# P04-NET.net
KiCad netlist of a schematic drawn in Altium Designer
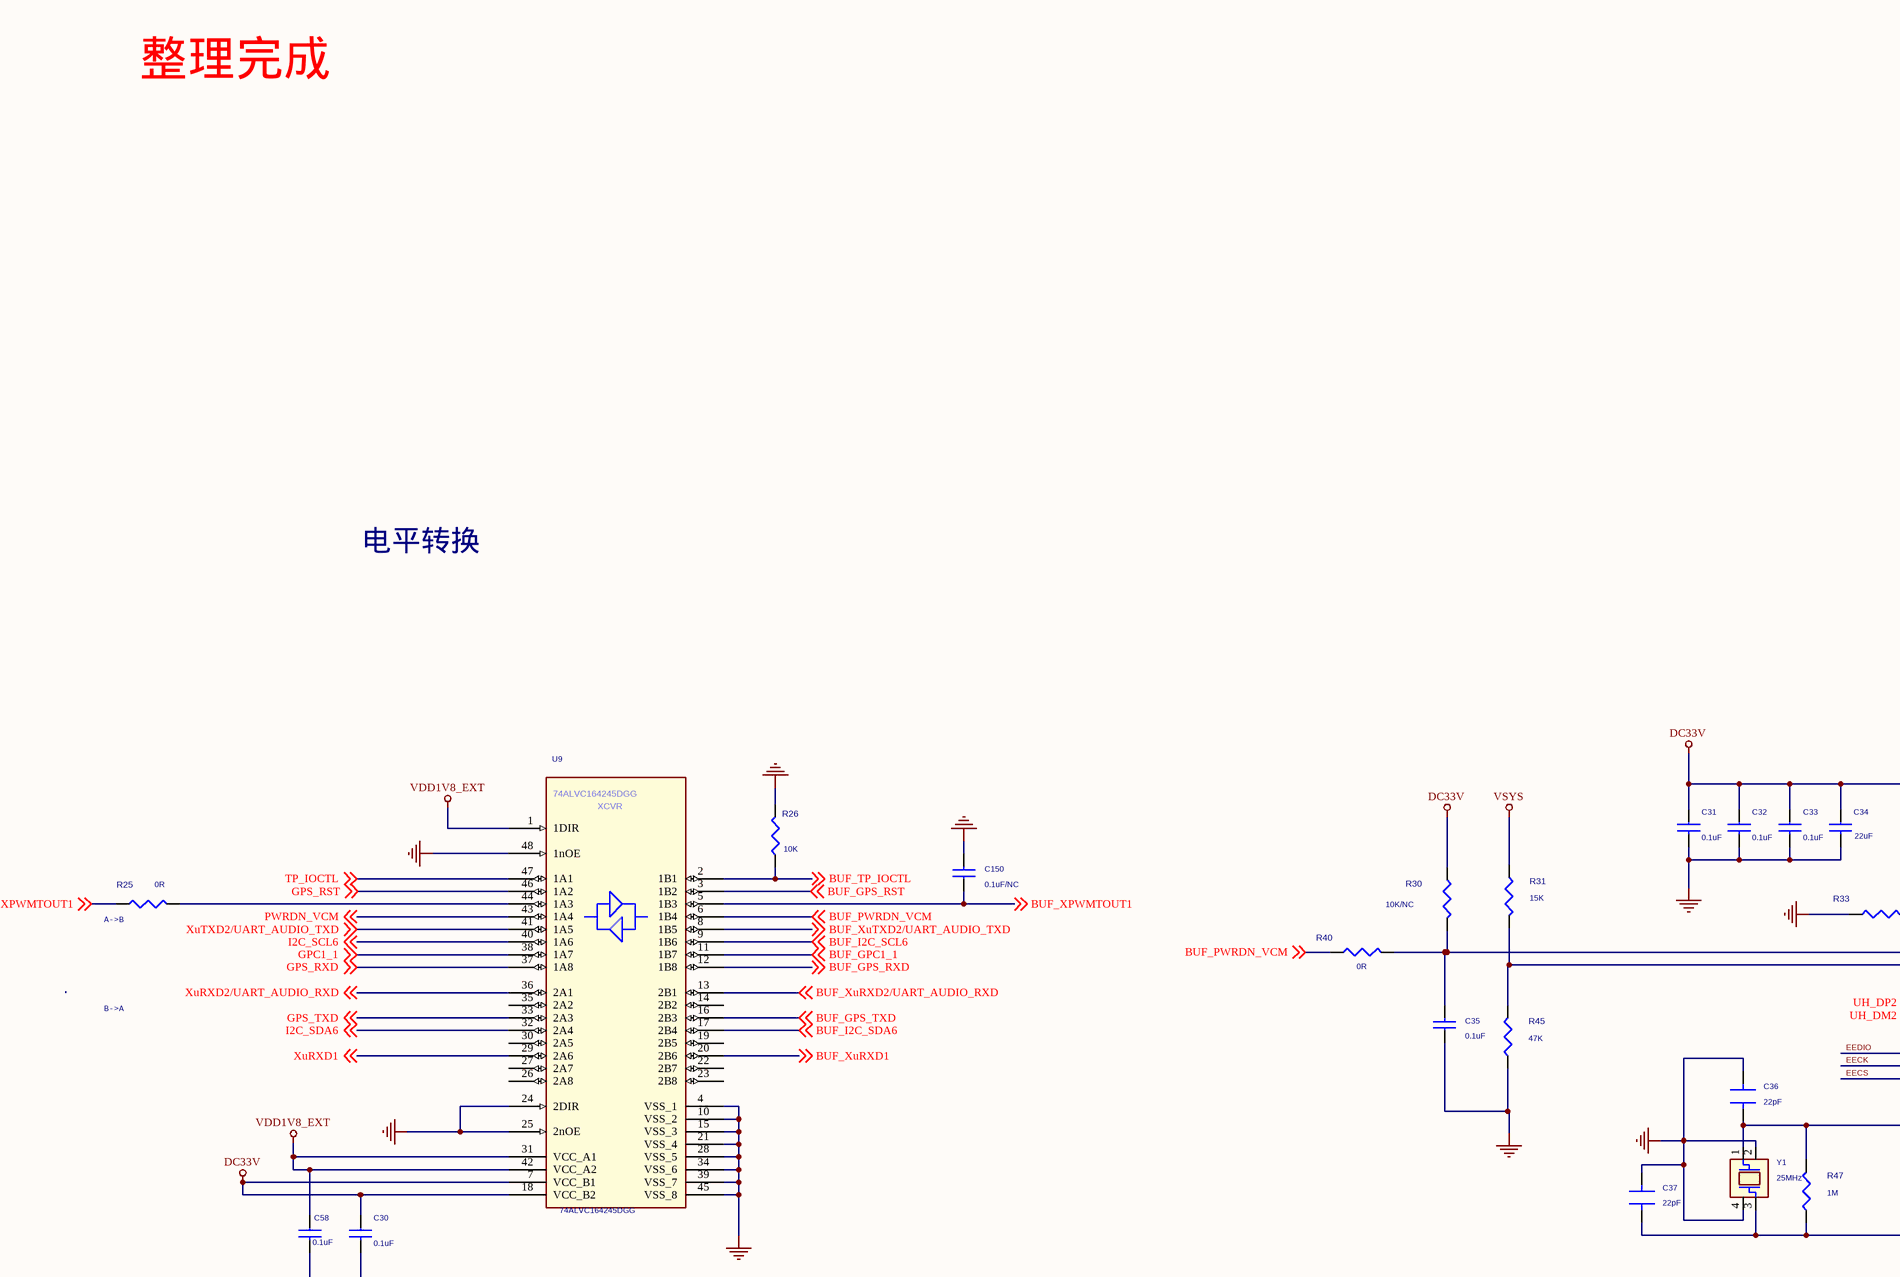
[diagram p0: P04-NET.SchDoc, top left]
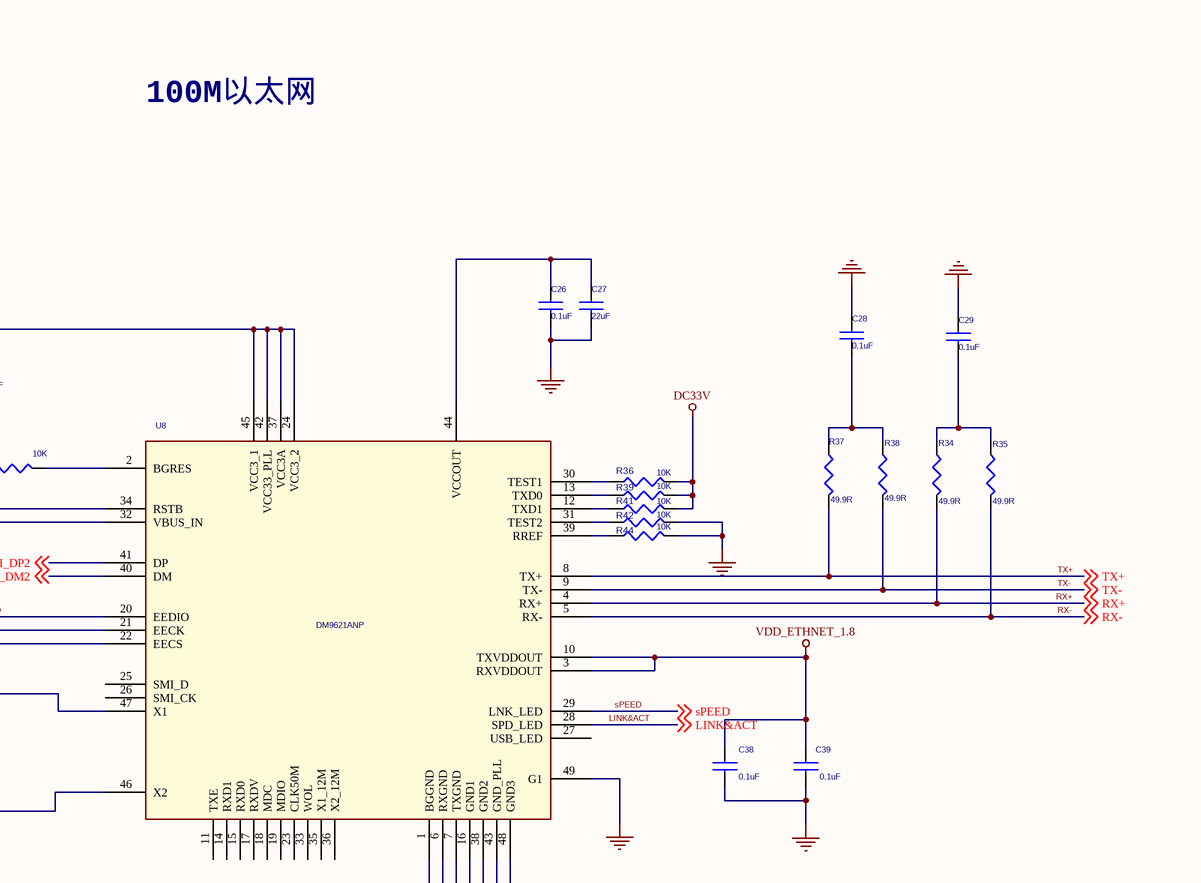
[diagram p1: P04-NET.SchDoc, top right]
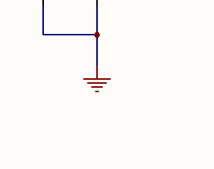
[diagram p2: P04-NET.SchDoc, bottom left]
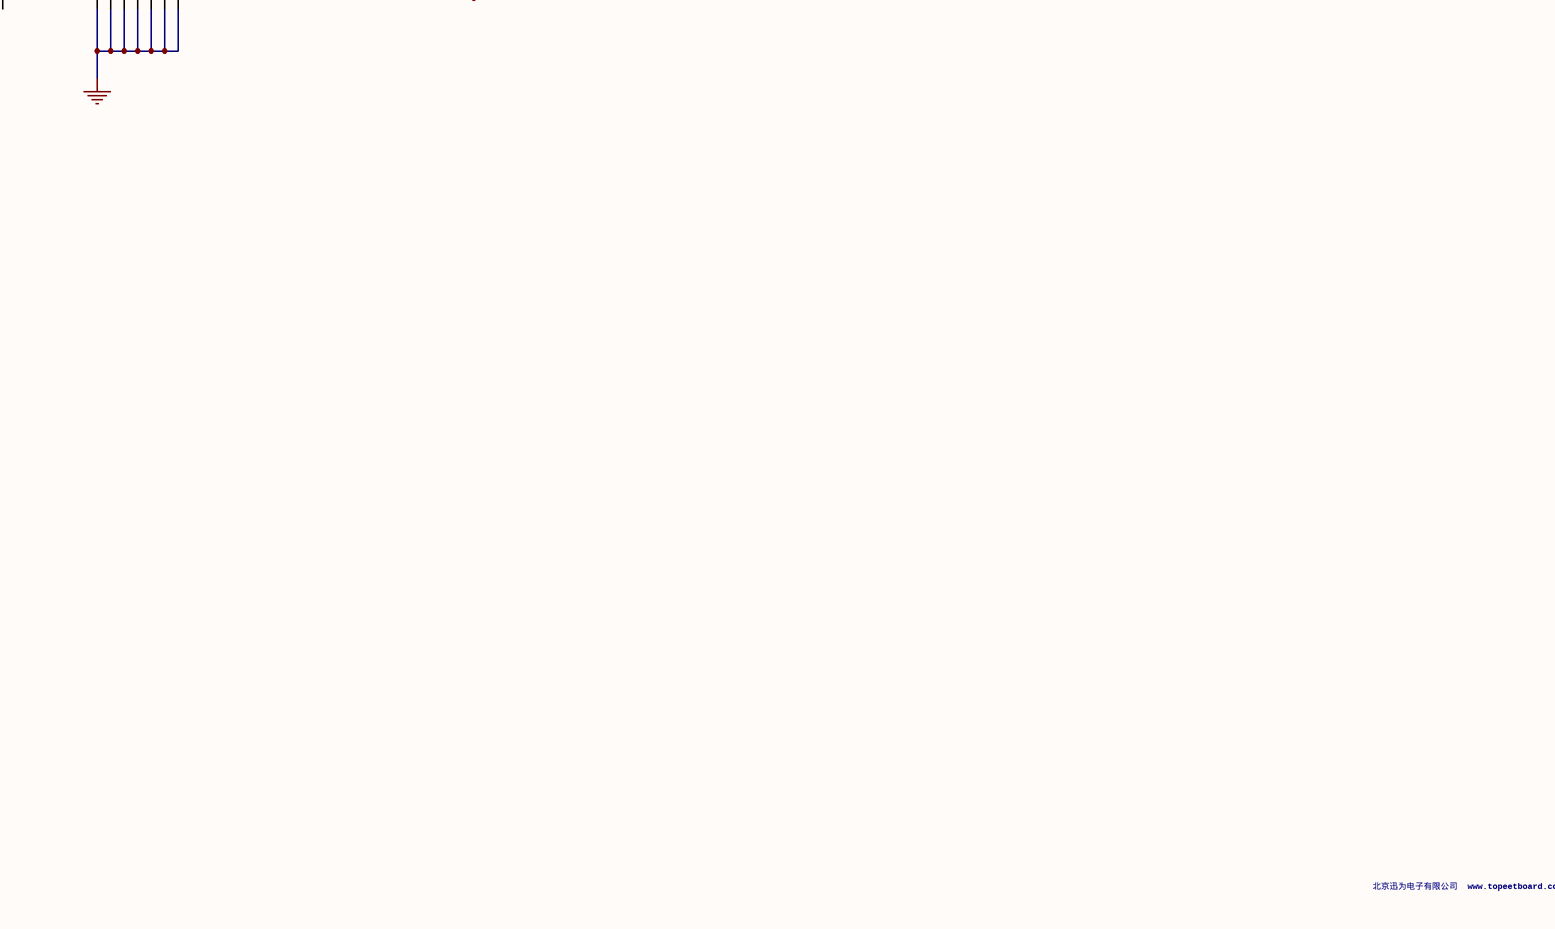
[diagram p3: P04-NET.SchDoc, bottom right]

(export (version "E")
  (design (tool "Eeschema 10.0.6"))
  (components
    (comp (ref "C26") (value "0.1uF") (footprint "C0603-S") (libsource (lib "*") (part "C1608_Dup1")))
    (comp (ref "C27") (value "22uF") (footprint "C1206-S") (libsource (lib "*") (part "C1206_0")))
    (comp (ref "C28") (value "0.1uF") (footprint "C0603-S") (libsource (lib "*") (part "C1608_Dup1")))
    (comp (ref "C29") (value "0.1uF") (footprint "C0603-S") (libsource (lib "*") (part "C1608_Dup1")))
    (comp (ref "C30") (value "0.1uF") (footprint "C0603-S") (libsource (lib "*") (part "C1608_Dup1")))
    (comp (ref "C31") (value "0.1uF") (footprint "C0603-S") (libsource (lib "*") (part "C1608_Dup1")))
    (comp (ref "C32") (value "0.1uF") (footprint "C0603-S") (libsource (lib "*") (part "C1608_Dup1")))
    (comp (ref "C33") (value "0.1uF") (footprint "C0603-S") (libsource (lib "*") (part "C1608_Dup1")))
    (comp (ref "C34") (value "22uF") (footprint "C1206-S") (libsource (lib "*") (part "C1206_0")))
    (comp (ref "C35") (value "0.1uF") (footprint "C0603-S") (libsource (lib "*") (part "C1608_Dup1")))
    (comp (ref "C36") (value "22pF") (footprint "C0603-S") (libsource (lib "*") (part "CAP_1")))
    (comp (ref "C37") (value "22pF") (footprint "C0603-S") (libsource (lib "*") (part "CAP_1")))
    (comp (ref "C38") (value "0.1uF") (footprint "C0603-S") (libsource (lib "*") (part "C1608_Dup1")))
    (comp (ref "C39") (value "0.1uF") (footprint "C0603-S") (libsource (lib "*") (part "C1608_Dup1")))
    (comp (ref "C58") (value "0.1uF") (footprint "C0603-S") (libsource (lib "*") (part "C0402_0")))
    (comp (ref "C150") (value "0.1uF/NC") (footprint "C0603-S") (libsource (lib "*") (part "C1608_Dup1")))
    (comp (ref "R25") (value "0R") (footprint "R0603-S") (libsource (lib "*") (part "RESISTOR_0")))
    (comp (ref "R26") (value "10K") (footprint "R0603-S") (libsource (lib "*") (part "RESISTOR_0")))
    (comp (ref "R30") (value "10K/NC") (footprint "R0603-S") (libsource (lib "*") (part "RESISTOR_0")))
    (comp (ref "R31") (value "15K") (footprint "R0603-S") (libsource (lib "*") (part "RESISTOR_0")))
    (comp (ref "R33") (value "10K") (footprint "R0603-S") (libsource (lib "*") (part "RESISTOR_0")))
    (comp (ref "R34") (value "49.9R") (footprint "R0805-S") (libsource (lib "*") (part "R_Dup2")))
    (comp (ref "R35") (value "49.9R") (footprint "R0805-S") (libsource (lib "*") (part "R_Dup2")))
    (comp (ref "R36") (value "10K") (footprint "R0603-S") (libsource (lib "*") (part "RESISTOR_0")))
    (comp (ref "R37") (value "49.9R") (footprint "R0805-S") (libsource (lib "*") (part "R_Dup2")))
    (comp (ref "R38") (value "49.9R") (footprint "R0805-S") (libsource (lib "*") (part "R_Dup2")))
    (comp (ref "R39") (value "10K") (footprint "R0603-S") (libsource (lib "*") (part "RESISTOR_0")))
    (comp (ref "R40") (value "0R") (footprint "R0603-S") (libsource (lib "*") (part "RESISTOR_0")))
    (comp (ref "R41") (value "10K") (footprint "R0603-S") (libsource (lib "*") (part "RESISTOR_0")))
    (comp (ref "R42") (value "10K") (footprint "R0603-S") (libsource (lib "*") (part "RESISTOR_0")))
    (comp (ref "R44") (value "10K") (footprint "R0603-S") (libsource (lib "*") (part "RESISTOR_0")))
    (comp (ref "R45") (value "47K") (footprint "R0603-S") (libsource (lib "*") (part "RESISTOR_0")))
    (comp (ref "R47") (value "1M") (footprint "R0603-S") (libsource (lib "*") (part "RESISTOR_0")))
    (comp (ref "U8")
      (value "DM9621ANP")
      (footprint "QFN48-050-0707LH")
      (libsource (lib "*") (part "DM9621NP_1"))
    )
    (comp (ref "U9")
      (value "U-74ALVC164245DGG")
      (footprint "TSSOP_48")
      (fields (field (name "PART_NUMBER") "74ALVC164245DGG"))
      (libsource (lib "*") (part "U-74ALVC164245DGG"))
    )
    (comp (ref "Y1") (value "25MHz") (footprint "X4-2_5X3_2") (libsource (lib "*") (part "Y_24.576MHZ-5032")))
  )
  (nets
    (net (code "1") (name "/EECK") (class "Default")
      (node (ref "U8") (pin "21") (pinfunction "EECK_21") (pintype "passive"))
    )
    (net (code "2") (name "/EECS") (class "Default")
      (node (ref "U8") (pin "22") (pinfunction "EECS_22") (pintype "passive"))
    )
    (net (code "3") (name "/EEDIO") (class "Default")
      (node (ref "U8") (pin "20") (pinfunction "EEDIO_20") (pintype "passive"))
    )
    (net (code "4") (name "BUF_GPC1_1") (class "Default")
      (node (ref "U9") (pin "11") (pinfunction "1B7_11") (pintype "bidirectional"))
    )
    (net (code "5") (name "BUF_GPS_RST") (class "Default")
      (node (ref "U9") (pin "3") (pinfunction "1B2_3") (pintype "bidirectional"))
    )
    (net (code "6") (name "BUF_GPS_RXD") (class "Default")
      (node (ref "U9") (pin "12") (pinfunction "1B8_12") (pintype "bidirectional"))
    )
    (net (code "7") (name "BUF_GPS_TXD") (class "Default")
      (node (ref "U9") (pin "16") (pinfunction "2B3_16") (pintype "bidirectional"))
    )
    (net (code "8") (name "BUF_I2C_SCL6") (class "Default")
      (node (ref "U9") (pin "9") (pinfunction "1B6_9") (pintype "bidirectional"))
    )
    (net (code "9") (name "BUF_I2C_SDA6") (class "Default")
      (node (ref "U9") (pin "17") (pinfunction "2B4_17") (pintype "bidirectional"))
    )
    (net (code "10") (name "BUF_PWRDN_VCM") (class "Default")
      (node (ref "R40") (pin "2") (pinfunction "2_2") (pintype "passive"))
      (node (ref "U9") (pin "6") (pinfunction "1B4_6") (pintype "bidirectional"))
    )
    (net (code "11") (name "BUF_TP_IOCTL") (class "Default")
      (node (ref "R26") (pin "2") (pinfunction "2_2") (pintype "passive"))
      (node (ref "U9") (pin "2") (pinfunction "1B1_2") (pintype "bidirectional"))
    )
    (net (code "12") (name "BUF_XPWMTOUT1") (class "Default")
      (node (ref "C150") (pin "1") (pinfunction "1_1") (pintype "passive"))
      (node (ref "U9") (pin "5") (pinfunction "1B3_5") (pintype "bidirectional"))
    )
    (net (code "13") (name "BUF_XuRXD1") (class "Default")
      (node (ref "U9") (pin "20") (pinfunction "2B6_20") (pintype "bidirectional"))
    )
    (net (code "14") (name "BUF_XuRXD2{slash}UART_AUDIO_RXD") (class "Default")
      (node (ref "U9") (pin "13") (pinfunction "2B1_13") (pintype "bidirectional"))
    )
    (net (code "15") (name "BUF_XuTXD2{slash}UART_AUDIO_TXD") (class "Default")
      (node (ref "U9") (pin "8") (pinfunction "1B5_8") (pintype "bidirectional"))
    )
    (net (code "16") (name "DC33V") (class "Default")
      (node (ref "C30") (pin "1") (pinfunction "1_1") (pintype "passive"))
      (node (ref "C31") (pin "1") (pinfunction "1_1") (pintype "passive"))
      (node (ref "C32") (pin "1") (pinfunction "1_1") (pintype "passive"))
      (node (ref "C33") (pin "1") (pinfunction "1_1") (pintype "passive"))
      (node (ref "C34") (pin "1") (pinfunction "1_1") (pintype "passive"))
      (node (ref "R30") (pin "2") (pinfunction "2_2") (pintype "passive"))
      (node (ref "R36") (pin "1") (pinfunction "1_1") (pintype "passive"))
      (node (ref "R39") (pin "1") (pinfunction "1_1") (pintype "passive"))
      (node (ref "R41") (pin "1") (pinfunction "1_1") (pintype "passive"))
      (node (ref "U8") (pin "24") (pinfunction "VCC3_2_24") (pintype "passive"))
      (node (ref "U8") (pin "37") (pinfunction "VCC3A_37") (pintype "passive"))
      (node (ref "U8") (pin "42") (pinfunction "VCC33_PLL_42") (pintype "passive"))
      (node (ref "U8") (pin "45") (pinfunction "VCC3_1_45") (pintype "passive"))
      (node (ref "U9") (pin "18") (pinfunction "VCC_B2_18") (pintype "power_in"))
      (node (ref "U9") (pin "7") (pinfunction "VCC_B1_7") (pintype "power_in"))
    )
    (net (code "17") (name "GND") (class "Default")
      (node (ref "C150") (pin "2") (pinfunction "2_2") (pintype "passive"))
      (node (ref "C26") (pin "2") (pinfunction "2_2") (pintype "passive"))
      (node (ref "C27") (pin "2") (pinfunction "2_2") (pintype "passive"))
      (node (ref "C28") (pin "1") (pinfunction "1_1") (pintype "passive"))
      (node (ref "C29") (pin "1") (pinfunction "1_1") (pintype "passive"))
      (node (ref "C30") (pin "2") (pinfunction "2_2") (pintype "passive"))
      (node (ref "C31") (pin "2") (pinfunction "2_2") (pintype "passive"))
      (node (ref "C32") (pin "2") (pinfunction "2_2") (pintype "passive"))
      (node (ref "C33") (pin "2") (pinfunction "2_2") (pintype "passive"))
      (node (ref "C34") (pin "2") (pinfunction "2_2") (pintype "passive"))
      (node (ref "C35") (pin "1") (pinfunction "1_1") (pintype "passive"))
      (node (ref "C36") (pin "2") (pinfunction "2_2") (pintype "passive"))
      (node (ref "C37") (pin "2") (pinfunction "2_2") (pintype "passive"))
      (node (ref "C38") (pin "2") (pinfunction "2_2") (pintype "passive"))
      (node (ref "C39") (pin "2") (pinfunction "2_2") (pintype "passive"))
      (node (ref "C58") (pin "2") (pinfunction "2_2") (pintype "passive"))
      (node (ref "R26") (pin "1") (pinfunction "1_1") (pintype "passive"))
      (node (ref "R33") (pin "2") (pinfunction "2_2") (pintype "passive"))
      (node (ref "R42") (pin "1") (pinfunction "1_1") (pintype "passive"))
      (node (ref "R44") (pin "1") (pinfunction "1_1") (pintype "passive"))
      (node (ref "R45") (pin "2") (pinfunction "2_2") (pintype "passive"))
      (node (ref "U8") (pin "1") (pinfunction "BGGND_1") (pintype "passive"))
      (node (ref "U8") (pin "16") (pinfunction "GND1_16") (pintype "passive"))
      (node (ref "U8") (pin "38") (pinfunction "GND2_38") (pintype "passive"))
      (node (ref "U8") (pin "43") (pinfunction "GND_PLL_43") (pintype "passive"))
      (node (ref "U8") (pin "48") (pinfunction "GND3_48") (pintype "passive"))
      (node (ref "U8") (pin "49") (pinfunction "G1_49") (pintype "passive"))
      (node (ref "U8") (pin "6") (pinfunction "RXGND_6") (pintype "passive"))
      (node (ref "U8") (pin "7") (pinfunction "TXGND_7") (pintype "passive"))
      (node (ref "U9") (pin "10") (pinfunction "VSS_2_10") (pintype "passive"))
      (node (ref "U9") (pin "15") (pinfunction "VSS_3_15") (pintype "passive"))
      (node (ref "U9") (pin "21") (pinfunction "VSS_4_21") (pintype "passive"))
      (node (ref "U9") (pin "24") (pinfunction "2DIR_24") (pintype "input"))
      (node (ref "U9") (pin "25") (pinfunction "2nOE_25") (pintype "input"))
      (node (ref "U9") (pin "28") (pinfunction "VSS_5_28") (pintype "passive"))
      (node (ref "U9") (pin "34") (pinfunction "VSS_6_34") (pintype "passive"))
      (node (ref "U9") (pin "39") (pinfunction "VSS_7_39") (pintype "passive"))
      (node (ref "U9") (pin "4") (pinfunction "VSS_1_4") (pintype "passive"))
      (node (ref "U9") (pin "45") (pinfunction "VSS_8_45") (pintype "passive"))
      (node (ref "U9") (pin "48") (pinfunction "1nOE_48") (pintype "input"))
      (node (ref "Y1") (pin "2") (pinfunction "GND_2") (pintype "power_in"))
      (node (ref "Y1") (pin "4") (pinfunction "GND_4") (pintype "power_in"))
    )
    (net (code "18") (name "GPC1_1") (class "Default")
      (node (ref "U9") (pin "38") (pinfunction "1A7_38") (pintype "bidirectional"))
    )
    (net (code "19") (name "GPS_RST") (class "Default")
      (node (ref "U9") (pin "46") (pinfunction "1A2_46") (pintype "bidirectional"))
    )
    (net (code "20") (name "GPS_RXD") (class "Default")
      (node (ref "U9") (pin "37") (pinfunction "1A8_37") (pintype "bidirectional"))
    )
    (net (code "21") (name "GPS_TXD") (class "Default")
      (node (ref "U9") (pin "33") (pinfunction "2A3_33") (pintype "bidirectional"))
    )
    (net (code "22") (name "I2C_SCL6") (class "Default")
      (node (ref "U9") (pin "40") (pinfunction "1A6_40") (pintype "bidirectional"))
    )
    (net (code "23") (name "I2C_SDA6") (class "Default")
      (node (ref "U9") (pin "32") (pinfunction "2A4_32") (pintype "bidirectional"))
    )
    (net (code "24") (name "LINK&ACT") (class "Default")
      (node (ref "U8") (pin "28") (pinfunction "SPD_LED_28") (pintype "passive"))
    )
    (net (code "25") (name "Net-(C28-Pad2)") (class "Default")
      (node (ref "C28") (pin "2") (pinfunction "2_2") (pintype "passive"))
      (node (ref "R37") (pin "2") (pinfunction "2_2") (pintype "passive"))
      (node (ref "R38") (pin "2") (pinfunction "2_2") (pintype "passive"))
    )
    (net (code "26") (name "Net-(C29-Pad2)") (class "Default")
      (node (ref "C29") (pin "2") (pinfunction "2_2") (pintype "passive"))
      (node (ref "R34") (pin "2") (pinfunction "2_2") (pintype "passive"))
      (node (ref "R35") (pin "2") (pinfunction "2_2") (pintype "passive"))
    )
    (net (code "27") (name "Net-(U8-BGRES)") (class "Default")
      (node (ref "R33") (pin "1") (pinfunction "1_1") (pintype "passive"))
      (node (ref "U8") (pin "2") (pinfunction "BGRES_2") (pintype "passive"))
    )
    (net (code "28") (name "Net-(U8-RREF)") (class "Default")
      (node (ref "R44") (pin "2") (pinfunction "2_2") (pintype "passive"))
      (node (ref "U8") (pin "39") (pinfunction "RREF_39") (pintype "passive"))
    )
    (net (code "29") (name "Net-(U8-RSTB)") (class "Default")
      (node (ref "C35") (pin "2") (pinfunction "2_2") (pintype "passive"))
      (node (ref "R30") (pin "1") (pinfunction "1_1") (pintype "passive"))
      (node (ref "R40") (pin "1") (pinfunction "1_1") (pintype "passive"))
      (node (ref "U8") (pin "34") (pinfunction "RSTB_34") (pintype "passive"))
    )
    (net (code "30") (name "Net-(U8-TEST1)") (class "Default")
      (node (ref "R36") (pin "2") (pinfunction "2_2") (pintype "passive"))
      (node (ref "U8") (pin "30") (pinfunction "TEST1_30") (pintype "passive"))
    )
    (net (code "31") (name "Net-(U8-TEST2)") (class "Default")
      (node (ref "R42") (pin "2") (pinfunction "2_2") (pintype "passive"))
      (node (ref "U8") (pin "31") (pinfunction "TEST2_31") (pintype "passive"))
    )
    (net (code "32") (name "Net-(U8-TXD0)") (class "Default")
      (node (ref "R39") (pin "2") (pinfunction "2_2") (pintype "passive"))
      (node (ref "U8") (pin "13") (pinfunction "TXD0_13") (pintype "passive"))
    )
    (net (code "33") (name "Net-(U8-TXD1)") (class "Default")
      (node (ref "R41") (pin "2") (pinfunction "2_2") (pintype "passive"))
      (node (ref "U8") (pin "12") (pinfunction "TXD1_12") (pintype "passive"))
    )
    (net (code "34") (name "Net-(U8-VBUS_IN)") (class "Default")
      (node (ref "R31") (pin "1") (pinfunction "1_1") (pintype "passive"))
      (node (ref "R45") (pin "1") (pinfunction "1_1") (pintype "passive"))
      (node (ref "U8") (pin "32") (pinfunction "VBUS_IN_32") (pintype "passive"))
    )
    (net (code "35") (name "Net-(U8-VCCOUT)") (class "Default")
      (node (ref "C26") (pin "1") (pinfunction "1_1") (pintype "passive"))
      (node (ref "C27") (pin "1") (pinfunction "1_1") (pintype "passive"))
      (node (ref "U8") (pin "44") (pinfunction "VCCOUT_44") (pintype "passive"))
    )
    (net (code "36") (name "Net-(U8-X1)") (class "Default")
      (node (ref "C36") (pin "1") (pinfunction "1_1") (pintype "passive"))
      (node (ref "R47") (pin "1") (pinfunction "1_1") (pintype "passive"))
      (node (ref "U8") (pin "47") (pinfunction "X1_47") (pintype "passive"))
      (node (ref "Y1") (pin "1") (pinfunction "CIN_1") (pintype "passive"))
    )
    (net (code "37") (name "Net-(U8-X2)") (class "Default")
      (node (ref "C37") (pin "1") (pinfunction "1_1") (pintype "passive"))
      (node (ref "R47") (pin "2") (pinfunction "2_2") (pintype "passive"))
      (node (ref "U8") (pin "46") (pinfunction "X2_46") (pintype "passive"))
      (node (ref "Y1") (pin "3") (pinfunction "COUT_3") (pintype "passive"))
    )
    (net (code "38") (name "Net-(U9-1A3)") (class "Default")
      (node (ref "R25") (pin "1") (pinfunction "1_1") (pintype "passive"))
      (node (ref "U9") (pin "44") (pinfunction "1A3_44") (pintype "bidirectional"))
    )
    (net (code "39") (name "PWRDN_VCM") (class "Default")
      (node (ref "U9") (pin "43") (pinfunction "1A4_43") (pintype "bidirectional"))
    )
    (net (code "40") (name "RX+") (class "Default")
      (node (ref "R34") (pin "1") (pinfunction "1_1") (pintype "passive"))
      (node (ref "U8") (pin "4") (pinfunction "RX+_4") (pintype "passive"))
    )
    (net (code "41") (name "RX-") (class "Default")
      (node (ref "R35") (pin "1") (pinfunction "1_1") (pintype "passive"))
      (node (ref "U8") (pin "5") (pinfunction "RX-_5") (pintype "passive"))
    )
    (net (code "42") (name "TP_IOCTL") (class "Default")
      (node (ref "U9") (pin "47") (pinfunction "1A1_47") (pintype "bidirectional"))
    )
    (net (code "43") (name "TX+") (class "Default")
      (node (ref "R37") (pin "1") (pinfunction "1_1") (pintype "passive"))
      (node (ref "U8") (pin "8") (pinfunction "TX+_8") (pintype "passive"))
    )
    (net (code "44") (name "TX-") (class "Default")
      (node (ref "R38") (pin "1") (pinfunction "1_1") (pintype "passive"))
      (node (ref "U8") (pin "9") (pinfunction "TX-_9") (pintype "passive"))
    )
    (net (code "45") (name "UH_DM2") (class "Default")
      (node (ref "U8") (pin "40") (pinfunction "DM_40") (pintype "passive"))
    )
    (net (code "46") (name "UH_DP2") (class "Default")
      (node (ref "U8") (pin "41") (pinfunction "DP_41") (pintype "passive"))
    )
    (net (code "47") (name "VDD1V8_EXT") (class "Default")
      (node (ref "C58") (pin "1") (pinfunction "1_1") (pintype "passive"))
      (node (ref "U9") (pin "1") (pinfunction "1DIR_1") (pintype "input"))
      (node (ref "U9") (pin "31") (pinfunction "VCC_A1_31") (pintype "power_in"))
      (node (ref "U9") (pin "42") (pinfunction "VCC_A2_42") (pintype "power_in"))
    )
    (net (code "48") (name "VDD_ETHNET_1.8") (class "Default")
      (node (ref "C38") (pin "1") (pinfunction "1_1") (pintype "passive"))
      (node (ref "C39") (pin "1") (pinfunction "1_1") (pintype "passive"))
      (node (ref "U8") (pin "10") (pinfunction "TXVDDOUT_10") (pintype "passive"))
      (node (ref "U8") (pin "3") (pinfunction "RXVDDOUT_3") (pintype "passive"))
    )
    (net (code "49") (name "VSYS") (class "Default")
      (node (ref "R31") (pin "2") (pinfunction "2_2") (pintype "passive"))
    )
    (net (code "50") (name "XPWMTOUT1") (class "Default")
      (node (ref "R25") (pin "2") (pinfunction "2_2") (pintype "passive"))
    )
    (net (code "51") (name "XuRXD1") (class "Default")
      (node (ref "U9") (pin "29") (pinfunction "2A6_29") (pintype "bidirectional"))
    )
    (net (code "52") (name "XuRXD2{slash}UART_AUDIO_RXD") (class "Default")
      (node (ref "U9") (pin "36") (pinfunction "2A1_36") (pintype "bidirectional"))
    )
    (net (code "53") (name "XuTXD2{slash}UART_AUDIO_TXD") (class "Default")
      (node (ref "U9") (pin "41") (pinfunction "1A5_41") (pintype "bidirectional"))
    )
    (net (code "54") (name "sPEED") (class "Default")
      (node (ref "U8") (pin "29") (pinfunction "LNK_LED_29") (pintype "passive"))
    )
    (net (code "55") (name "unconnected-(U8-CLK50M-Pad23)") (class "Default")
      (node (ref "U8") (pin "23") (pinfunction "CLK50M_23") (pintype "passive"))
    )
    (net (code "56") (name "unconnected-(U8-MDC-Pad18)") (class "Default")
      (node (ref "U8") (pin "18") (pinfunction "MDC_18") (pintype "passive"))
    )
    (net (code "57") (name "unconnected-(U8-MDIO-Pad19)") (class "Default")
      (node (ref "U8") (pin "19") (pinfunction "MDIO_19") (pintype "passive"))
    )
    (net (code "58") (name "unconnected-(U8-RXD0-Pad15)") (class "Default")
      (node (ref "U8") (pin "15") (pinfunction "RXD0_15") (pintype "passive"))
    )
    (net (code "59") (name "unconnected-(U8-RXD1-Pad14)") (class "Default")
      (node (ref "U8") (pin "14") (pinfunction "RXD1_14") (pintype "passive"))
    )
    (net (code "60") (name "unconnected-(U8-RXDV-Pad17)") (class "Default")
      (node (ref "U8") (pin "17") (pinfunction "RXDV_17") (pintype "passive"))
    )
    (net (code "61") (name "unconnected-(U8-SMI_CK-Pad26)") (class "Default")
      (node (ref "U8") (pin "26") (pinfunction "SMI_CK_26") (pintype "passive"))
    )
    (net (code "62") (name "unconnected-(U8-SMI_D-Pad25)") (class "Default")
      (node (ref "U8") (pin "25") (pinfunction "SMI_D_25") (pintype "passive"))
    )
    (net (code "63") (name "unconnected-(U8-TXE-Pad11)") (class "Default")
      (node (ref "U8") (pin "11") (pinfunction "TXE_11") (pintype "passive"))
    )
    (net (code "64") (name "unconnected-(U8-USB_LED-Pad27)") (class "Default")
      (node (ref "U8") (pin "27") (pinfunction "USB_LED_27") (pintype "passive"))
    )
    (net (code "65") (name "unconnected-(U8-WOL-Pad33)") (class "Default")
      (node (ref "U8") (pin "33") (pinfunction "WOL_33") (pintype "passive"))
    )
    (net (code "66") (name "unconnected-(U8-X1_12M-Pad35)") (class "Default")
      (node (ref "U8") (pin "35") (pinfunction "X1_12M_35") (pintype "passive"))
    )
    (net (code "67") (name "unconnected-(U8-X2_12M-Pad36)") (class "Default")
      (node (ref "U8") (pin "36") (pinfunction "X2_12M_36") (pintype "passive"))
    )
    (net (code "68") (name "unconnected-(U9-2A2-Pad35)") (class "Default")
      (node (ref "U9") (pin "35") (pinfunction "2A2_35") (pintype "bidirectional"))
    )
    (net (code "69") (name "unconnected-(U9-2A5-Pad30)") (class "Default")
      (node (ref "U9") (pin "30") (pinfunction "2A5_30") (pintype "bidirectional"))
    )
    (net (code "70") (name "unconnected-(U9-2A7-Pad27)") (class "Default")
      (node (ref "U9") (pin "27") (pinfunction "2A7_27") (pintype "bidirectional"))
    )
    (net (code "71") (name "unconnected-(U9-2A8-Pad26)") (class "Default")
      (node (ref "U9") (pin "26") (pinfunction "2A8_26") (pintype "bidirectional"))
    )
    (net (code "72") (name "unconnected-(U9-2B2-Pad14)") (class "Default")
      (node (ref "U9") (pin "14") (pinfunction "2B2_14") (pintype "bidirectional"))
    )
    (net (code "73") (name "unconnected-(U9-2B5-Pad19)") (class "Default")
      (node (ref "U9") (pin "19") (pinfunction "2B5_19") (pintype "bidirectional"))
    )
    (net (code "74") (name "unconnected-(U9-2B7-Pad22)") (class "Default")
      (node (ref "U9") (pin "22") (pinfunction "2B7_22") (pintype "bidirectional"))
    )
    (net (code "75") (name "unconnected-(U9-2B8-Pad23)") (class "Default")
      (node (ref "U9") (pin "23") (pinfunction "2B8_23") (pintype "bidirectional"))
    )
  )
)
